# Teensy_Fan_Controller.net
KiCad netlist of a schematic drawn in EAGLE
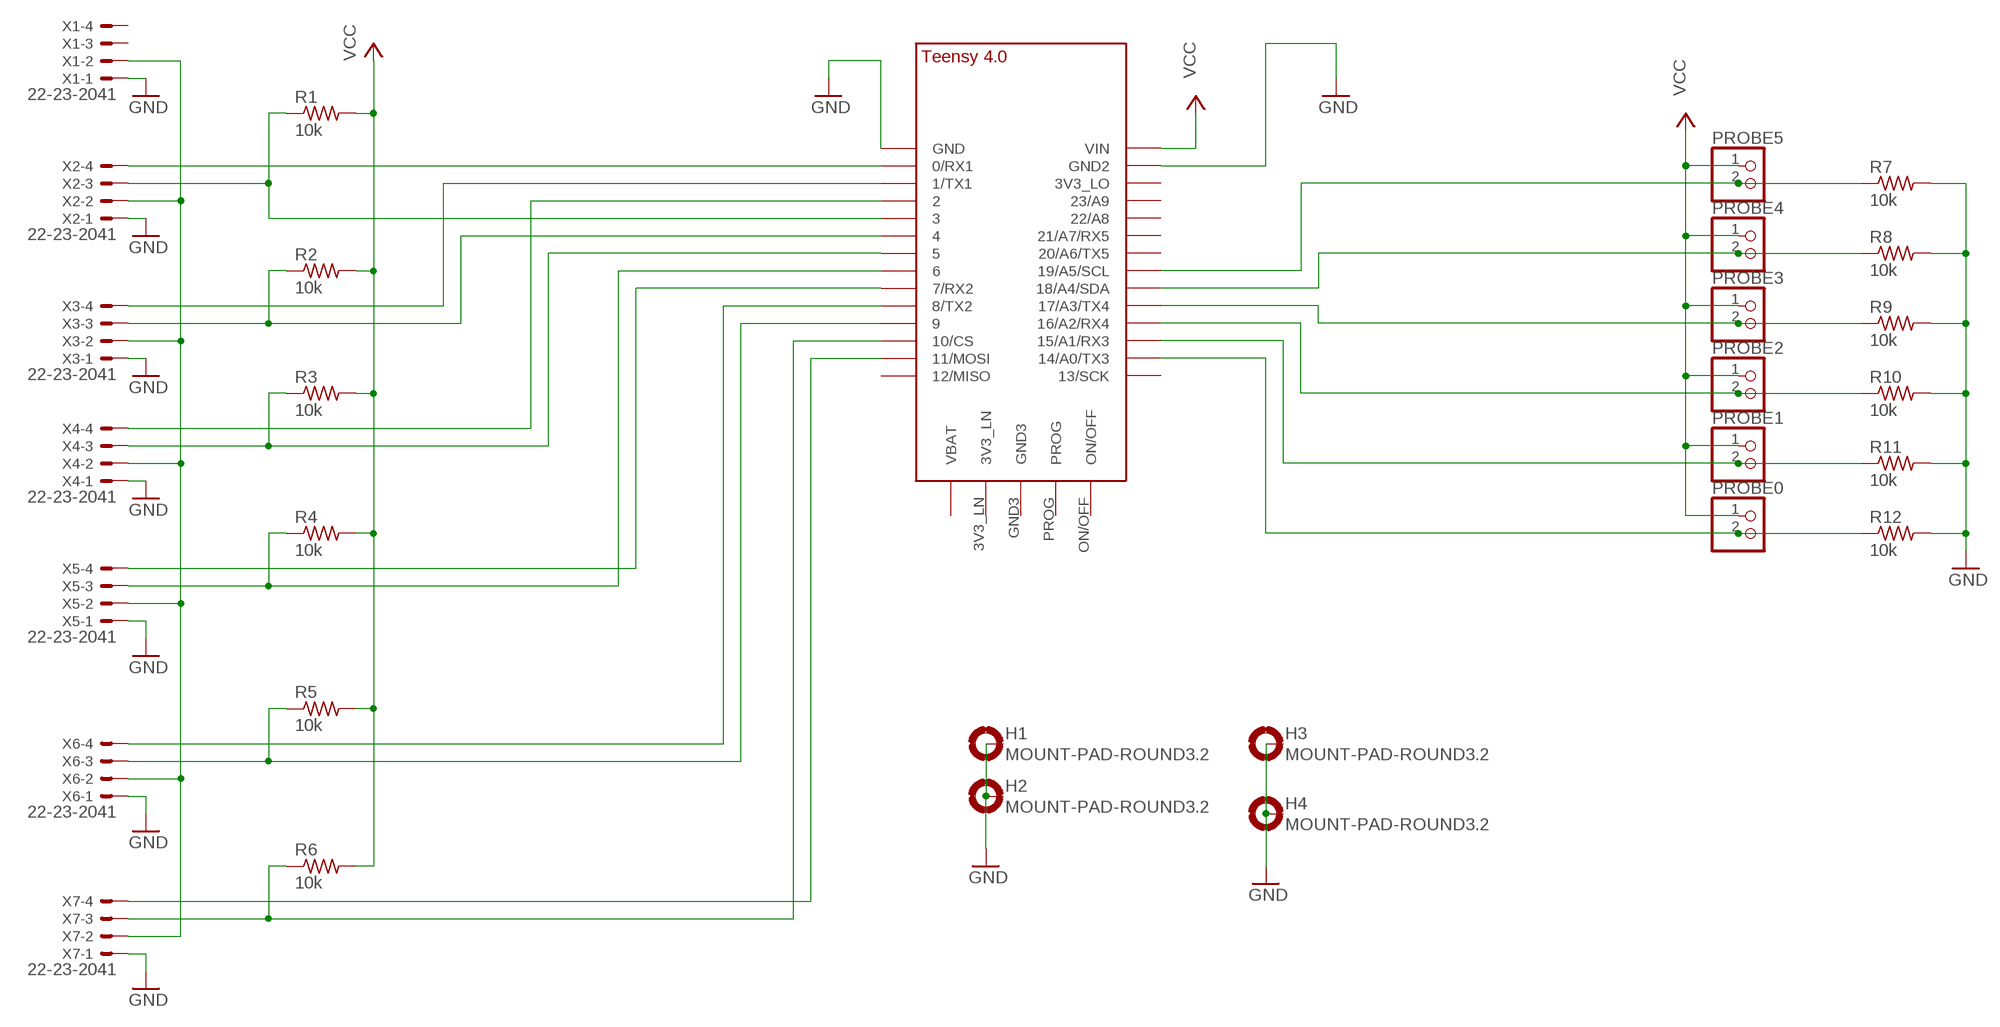
[diagram p0: schematic, sheet 1]

(export (version "E")
  (design (tool "Eeschema 10.0.6"))
  (components
    (comp (ref "H1")
      (value "MOUNT-PAD-ROUND3.2")
      (footprint "eagle-import:3,2-PAD")
      (libsource (lib "eagle-import") (part "MOUNT-PAD-ROUND3.2"))
    )
    (comp (ref "H2")
      (value "MOUNT-PAD-ROUND3.2")
      (footprint "eagle-import:3,2-PAD")
      (libsource (lib "eagle-import") (part "MOUNT-PAD-ROUND3.2"))
    )
    (comp (ref "H3")
      (value "MOUNT-PAD-ROUND3.2")
      (footprint "eagle-import:3,2-PAD")
      (libsource (lib "eagle-import") (part "MOUNT-PAD-ROUND3.2"))
    )
    (comp (ref "H4")
      (value "MOUNT-PAD-ROUND3.2")
      (footprint "eagle-import:3,2-PAD")
      (libsource (lib "eagle-import") (part "MOUNT-PAD-ROUND3.2"))
    )
    (comp (ref "PROBE0")
      (value "PINHD-1X2")
      (footprint "eagle-import:1X02")
      (libsource (lib "eagle-import") (part "PINHD-1X2"))
    )
    (comp (ref "PROBE1")
      (value "PINHD-1X2")
      (footprint "eagle-import:1X02")
      (libsource (lib "eagle-import") (part "PINHD-1X2"))
    )
    (comp (ref "PROBE2")
      (value "PINHD-1X2")
      (footprint "eagle-import:1X02")
      (libsource (lib "eagle-import") (part "PINHD-1X2"))
    )
    (comp (ref "PROBE3")
      (value "PINHD-1X2")
      (footprint "eagle-import:1X02")
      (libsource (lib "eagle-import") (part "PINHD-1X2"))
    )
    (comp (ref "PROBE4")
      (value "PINHD-1X2")
      (footprint "eagle-import:1X02")
      (libsource (lib "eagle-import") (part "PINHD-1X2"))
    )
    (comp (ref "PROBE5")
      (value "PINHD-1X2")
      (footprint "eagle-import:1X02")
      (libsource (lib "eagle-import") (part "PINHD-1X2"))
    )
    (comp (ref "R1")
      (value "10k")
      (footprint "eagle-import:0207_10")
      (libsource (lib "eagle-import") (part "R-US_0207/10"))
    )
    (comp (ref "R2")
      (value "10k")
      (footprint "eagle-import:0207_10")
      (libsource (lib "eagle-import") (part "R-US_0207/10"))
    )
    (comp (ref "R3")
      (value "10k")
      (footprint "eagle-import:0207_10")
      (libsource (lib "eagle-import") (part "R-US_0207/10"))
    )
    (comp (ref "R4")
      (value "10k")
      (footprint "eagle-import:0207_10")
      (libsource (lib "eagle-import") (part "R-US_0207/10"))
    )
    (comp (ref "R5")
      (value "10k")
      (footprint "eagle-import:0207_10")
      (libsource (lib "eagle-import") (part "R-US_0207/10"))
    )
    (comp (ref "R6")
      (value "10k")
      (footprint "eagle-import:0207_10")
      (libsource (lib "eagle-import") (part "R-US_0207/10"))
    )
    (comp (ref "R7")
      (value "10k")
      (footprint "eagle-import:0207_10")
      (libsource (lib "eagle-import") (part "R-US_0207/10"))
    )
    (comp (ref "R8")
      (value "10k")
      (footprint "eagle-import:0207_10")
      (libsource (lib "eagle-import") (part "R-US_0207/10"))
    )
    (comp (ref "R9")
      (value "10k")
      (footprint "eagle-import:0207_10")
      (libsource (lib "eagle-import") (part "R-US_0207/10"))
    )
    (comp (ref "R10")
      (value "10k")
      (footprint "eagle-import:0207_10")
      (libsource (lib "eagle-import") (part "R-US_0207/10"))
    )
    (comp (ref "R11")
      (value "10k")
      (footprint "eagle-import:0207_10")
      (libsource (lib "eagle-import") (part "R-US_0207/10"))
    )
    (comp (ref "R12")
      (value "10k")
      (footprint "eagle-import:0207_10")
      (libsource (lib "eagle-import") (part "R-US_0207/10"))
    )
    (comp (ref "U$2")
      (value "TEENSY_4.0")
      (footprint "eagle-import:TEENSY_4.0")
      (libsource (lib "eagle-import") (part "TEENSY_4.0"))
    )
    (comp (ref "X1")
      (value "22-23-2041")
      (footprint "eagle-import:22-23-2041")
      (fields (field (name "MF") "MOLEX"))
      (libsource (lib "eagle-import") (part "22-23-2041"))
    )
    (comp (ref "X2")
      (value "22-23-2041")
      (footprint "eagle-import:22-23-2041")
      (fields (field (name "MF") "MOLEX"))
      (libsource (lib "eagle-import") (part "22-23-2041"))
    )
    (comp (ref "X3")
      (value "22-23-2041")
      (footprint "eagle-import:22-23-2041")
      (fields (field (name "MF") "MOLEX"))
      (libsource (lib "eagle-import") (part "22-23-2041"))
    )
    (comp (ref "X4")
      (value "22-23-2041")
      (footprint "eagle-import:22-23-2041")
      (fields (field (name "MF") "MOLEX"))
      (libsource (lib "eagle-import") (part "22-23-2041"))
    )
    (comp (ref "X5")
      (value "22-23-2041")
      (footprint "eagle-import:22-23-2041")
      (fields (field (name "MF") "MOLEX"))
      (libsource (lib "eagle-import") (part "22-23-2041"))
    )
    (comp (ref "X6")
      (value "22-23-2041")
      (footprint "eagle-import:22-23-2041")
      (fields (field (name "MF") "MOLEX"))
      (libsource (lib "eagle-import") (part "22-23-2041"))
    )
    (comp (ref "X7")
      (value "22-23-2041")
      (footprint "eagle-import:22-23-2041")
      (fields (field (name "MF") "MOLEX"))
      (libsource (lib "eagle-import") (part "22-23-2041"))
    )
  )
  (nets
    (net (code "1") (name "GND") (class "Default")
      (node (ref "H1") (pin "B3,2") (pinfunction "MOUNT_B3,2") (pintype "passive"))
      (node (ref "H2") (pin "B3,2") (pinfunction "MOUNT_B3,2") (pintype "passive"))
      (node (ref "H3") (pin "B3,2") (pinfunction "MOUNT_B3,2") (pintype "passive"))
      (node (ref "H4") (pin "B3,2") (pinfunction "MOUNT_B3,2") (pintype "passive"))
      (node (ref "R10") (pin "2") (pinfunction "2_2") (pintype "passive"))
      (node (ref "R11") (pin "2") (pinfunction "2_2") (pintype "passive"))
      (node (ref "R12") (pin "2") (pinfunction "2_2") (pintype "passive"))
      (node (ref "R7") (pin "2") (pinfunction "2_2") (pintype "passive"))
      (node (ref "R8") (pin "2") (pinfunction "2_2") (pintype "passive"))
      (node (ref "R9") (pin "2") (pinfunction "2_2") (pintype "passive"))
      (node (ref "U$2") (pin "GND") (pinfunction "GND_GND") (pintype "bidirectional"))
      (node (ref "U$2") (pin "GND2") (pinfunction "GND2_GND2") (pintype "bidirectional"))
      (node (ref "X1") (pin "1") (pinfunction "S_1") (pintype "passive"))
      (node (ref "X2") (pin "1") (pinfunction "S_1") (pintype "passive"))
      (node (ref "X3") (pin "1") (pinfunction "S_1") (pintype "passive"))
      (node (ref "X4") (pin "1") (pinfunction "S_1") (pintype "passive"))
      (node (ref "X5") (pin "1") (pinfunction "S_1") (pintype "passive"))
      (node (ref "X6") (pin "1") (pinfunction "S_1") (pintype "passive"))
      (node (ref "X7") (pin "1") (pinfunction "S_1") (pintype "passive"))
    )
    (net (code "2") (name "Net-(PROBE4-Pad2)") (class "Default")
      (node (ref "PROBE4") (pin "2") (pinfunction "2_2") (pintype "passive"))
      (node (ref "R8") (pin "1") (pinfunction "1_1") (pintype "passive"))
      (node (ref "U$2") (pin "18/A4/SDA") (pinfunction "18/A4/SDA_18/A4/SDA") (pintype "bidirectional"))
    )
    (net (code "3") (name "Net-(PROBE5-Pad2)") (class "Default")
      (node (ref "PROBE5") (pin "2") (pinfunction "2_2") (pintype "passive"))
      (node (ref "R7") (pin "1") (pinfunction "1_1") (pintype "passive"))
      (node (ref "U$2") (pin "19/A5/SCL") (pinfunction "19/A5/SCL_19/A5/SCL") (pintype "bidirectional"))
    )
    (net (code "4") (name "Net-(U$2-0{slash}RX1)") (class "Default")
      (node (ref "U$2") (pin "0/RX") (pinfunction "0/RX1_0/RX") (pintype "bidirectional"))
      (node (ref "X2") (pin "4") (pinfunction "S_4") (pintype "passive"))
    )
    (net (code "5") (name "Net-(U$2-1{slash}TX1)") (class "Default")
      (node (ref "U$2") (pin "1/TX") (pinfunction "1/TX1_1/TX") (pintype "bidirectional"))
      (node (ref "X3") (pin "4") (pinfunction "S_4") (pintype "passive"))
    )
    (net (code "6") (name "Net-(U$2-3)") (class "Default")
      (node (ref "R1") (pin "1") (pinfunction "1_1") (pintype "passive"))
      (node (ref "U$2") (pin "3/CANTX") (pinfunction "3_3/CANTX") (pintype "bidirectional"))
      (node (ref "X2") (pin "3") (pinfunction "S_3") (pintype "passive"))
    )
    (net (code "7") (name "Net-(U$2-4)") (class "Default")
      (node (ref "R2") (pin "1") (pinfunction "1_1") (pintype "passive"))
      (node (ref "U$2") (pin "4/CANRX") (pinfunction "4_4/CANRX") (pintype "bidirectional"))
      (node (ref "X3") (pin "3") (pinfunction "S_3") (pintype "passive"))
    )
    (net (code "8") (name "Net-(U$2-7{slash}RX2)") (class "Default")
      (node (ref "U$2") (pin "7") (pinfunction "7/RX2_7") (pintype "bidirectional"))
      (node (ref "X5") (pin "4") (pinfunction "S_4") (pintype "passive"))
    )
    (net (code "9") (name "Net-(U$2-8{slash}TX2)") (class "Default")
      (node (ref "U$2") (pin "8") (pinfunction "8/TX2_8") (pintype "bidirectional"))
      (node (ref "X6") (pin "4") (pinfunction "S_4") (pintype "passive"))
    )
    (net (code "10") (name "Net-(U$2-9)") (class "Default")
      (node (ref "R5") (pin "1") (pinfunction "1_1") (pintype "passive"))
      (node (ref "U$2") (pin "9/CS") (pinfunction "9_9/CS") (pintype "bidirectional"))
      (node (ref "X6") (pin "3") (pinfunction "S_3") (pintype "passive"))
    )
    (net (code "11") (name "Net-(U$2-14{slash}A0{slash}TX3)") (class "Default")
      (node (ref "PROBE0") (pin "2") (pinfunction "2_2") (pintype "passive"))
      (node (ref "R12") (pin "1") (pinfunction "1_1") (pintype "passive"))
      (node (ref "U$2") (pin "14/A0") (pinfunction "14/A0/TX3_14/A0") (pintype "bidirectional"))
    )
    (net (code "12") (name "Net-(U$2-15{slash}A1{slash}RX3)") (class "Default")
      (node (ref "PROBE1") (pin "2") (pinfunction "2_2") (pintype "passive"))
      (node (ref "R11") (pin "1") (pinfunction "1_1") (pintype "passive"))
      (node (ref "U$2") (pin "15/A1") (pinfunction "15/A1/RX3_15/A1") (pintype "bidirectional"))
    )
    (net (code "13") (name "Net-(U$2-16{slash}A2{slash}RX4)") (class "Default")
      (node (ref "PROBE2") (pin "2") (pinfunction "2_2") (pintype "passive"))
      (node (ref "R10") (pin "1") (pinfunction "1_1") (pintype "passive"))
      (node (ref "U$2") (pin "16/A2") (pinfunction "16/A2/RX4_16/A2") (pintype "bidirectional"))
    )
    (net (code "14") (name "Net-(U$2-17{slash}A3{slash}TX4)") (class "Default")
      (node (ref "PROBE3") (pin "2") (pinfunction "2_2") (pintype "passive"))
      (node (ref "R9") (pin "1") (pinfunction "1_1") (pintype "passive"))
      (node (ref "U$2") (pin "17/A3") (pinfunction "17/A3/TX4_17/A3") (pintype "bidirectional"))
    )
    (net (code "15") (name "Net-(X1B-S)") (class "Default")
      (node (ref "X1") (pin "2") (pinfunction "S_2") (pintype "passive"))
      (node (ref "X2") (pin "2") (pinfunction "S_2") (pintype "passive"))
      (node (ref "X3") (pin "2") (pinfunction "S_2") (pintype "passive"))
      (node (ref "X4") (pin "2") (pinfunction "S_2") (pintype "passive"))
      (node (ref "X5") (pin "2") (pinfunction "S_2") (pintype "passive"))
      (node (ref "X6") (pin "2") (pinfunction "S_2") (pintype "passive"))
      (node (ref "X7") (pin "2") (pinfunction "S_2") (pintype "passive"))
    )
    (net (code "16") (name "Net-(X4C-S)") (class "Default")
      (node (ref "R3") (pin "1") (pinfunction "1_1") (pintype "passive"))
      (node (ref "U$2") (pin "5") (pinfunction "5_5") (pintype "bidirectional"))
      (node (ref "X4") (pin "3") (pinfunction "S_3") (pintype "passive"))
    )
    (net (code "17") (name "Net-(X4D-S)") (class "Default")
      (node (ref "U$2") (pin "2") (pinfunction "2_2") (pintype "bidirectional"))
      (node (ref "X4") (pin "4") (pinfunction "S_4") (pintype "passive"))
    )
    (net (code "18") (name "Net-(X5C-S)") (class "Default")
      (node (ref "R4") (pin "1") (pinfunction "1_1") (pintype "passive"))
      (node (ref "U$2") (pin "6") (pinfunction "6_6") (pintype "bidirectional"))
      (node (ref "X5") (pin "3") (pinfunction "S_3") (pintype "passive"))
    )
    (net (code "19") (name "Net-(X7C-S)") (class "Default")
      (node (ref "R6") (pin "1") (pinfunction "1_1") (pintype "passive"))
      (node (ref "U$2") (pin "10/CS") (pinfunction "10/CS_10/CS") (pintype "bidirectional"))
      (node (ref "X7") (pin "3") (pinfunction "S_3") (pintype "passive"))
    )
    (net (code "20") (name "Net-(X7D-S)") (class "Default")
      (node (ref "U$2") (pin "11/MOSI") (pinfunction "11/MOSI_11/MOSI") (pintype "bidirectional"))
      (node (ref "X7") (pin "4") (pinfunction "S_4") (pintype "passive"))
    )
    (net (code "21") (name "VCC") (class "Default")
      (node (ref "PROBE0") (pin "1") (pinfunction "1_1") (pintype "passive"))
      (node (ref "PROBE1") (pin "1") (pinfunction "1_1") (pintype "passive"))
      (node (ref "PROBE2") (pin "1") (pinfunction "1_1") (pintype "passive"))
      (node (ref "PROBE3") (pin "1") (pinfunction "1_1") (pintype "passive"))
      (node (ref "PROBE4") (pin "1") (pinfunction "1_1") (pintype "passive"))
      (node (ref "PROBE5") (pin "1") (pinfunction "1_1") (pintype "passive"))
      (node (ref "R1") (pin "2") (pinfunction "2_2") (pintype "passive"))
      (node (ref "R2") (pin "2") (pinfunction "2_2") (pintype "passive"))
      (node (ref "R3") (pin "2") (pinfunction "2_2") (pintype "passive"))
      (node (ref "R4") (pin "2") (pinfunction "2_2") (pintype "passive"))
      (node (ref "R5") (pin "2") (pinfunction "2_2") (pintype "passive"))
      (node (ref "R6") (pin "2") (pinfunction "2_2") (pintype "passive"))
      (node (ref "U$2") (pin "VIN") (pinfunction "VIN_VIN") (pintype "bidirectional"))
    )
    (net (code "22") (name "unconnected-(U$2-20{slash}A6{slash}TX5-Pad20{slash}A6)") (class "Default")
      (node (ref "U$2") (pin "20/A6") (pinfunction "20/A6/TX5_20/A6") (pintype "bidirectional"))
    )
    (net (code "23") (name "unconnected-(U$2-21{slash}A7{slash}RX5-Pad21{slash}A7)") (class "Default")
      (node (ref "U$2") (pin "21/A7") (pinfunction "21/A7/RX5_21/A7") (pintype "bidirectional"))
    )
    (net (code "24") (name "unconnected-(U$2-Pad3V3_LN)") (class "Default")
      (node (ref "U$2") (pin "3V3_LN") (pinfunction "3V3_LN_3V3_LN") (pintype "bidirectional"))
    )
    (net (code "25") (name "unconnected-(U$2-Pad3V3_LO)") (class "Default")
      (node (ref "U$2") (pin "3V3_LO") (pinfunction "3V3_LO_3V3_LO") (pintype "bidirectional"))
    )
    (net (code "26") (name "unconnected-(U$2-Pad12{slash}MISO)") (class "Default")
      (node (ref "U$2") (pin "12/MISO") (pinfunction "12/MISO_12/MISO") (pintype "bidirectional"))
    )
    (net (code "27") (name "unconnected-(U$2-Pad13{slash}SCK)") (class "Default")
      (node (ref "U$2") (pin "13/SCK") (pinfunction "13/SCK_13/SCK") (pintype "bidirectional"))
    )
    (net (code "28") (name "unconnected-(U$2-Pad22{slash}A8)") (class "Default")
      (node (ref "U$2") (pin "22/A8") (pinfunction "22/A8_22/A8") (pintype "bidirectional"))
    )
    (net (code "29") (name "unconnected-(U$2-Pad23{slash}A9)") (class "Default")
      (node (ref "U$2") (pin "23/A9") (pinfunction "23/A9_23/A9") (pintype "bidirectional"))
    )
    (net (code "30") (name "unconnected-(U$2-PadGND3)") (class "Default")
      (node (ref "U$2") (pin "GND3") (pinfunction "GND3_GND3") (pintype "bidirectional"))
    )
    (net (code "31") (name "unconnected-(U$2-PadON{slash}OFF)") (class "Default")
      (node (ref "U$2") (pin "ON/OFF") (pinfunction "ON/OFF_ON/OFF") (pintype "bidirectional"))
    )
    (net (code "32") (name "unconnected-(U$2-PadPROG)") (class "Default")
      (node (ref "U$2") (pin "PROG") (pinfunction "PROG_PROG") (pintype "bidirectional"))
    )
    (net (code "33") (name "unconnected-(U$2-VBAT-PadVBAT\\)") (class "Default")
      (node (ref "U$2") (pin "VBAT\\") (pinfunction "VBAT_VBAT\\") (pintype "bidirectional"))
    )
    (net (code "34") (name "unconnected-(X1C-S-Pad3)") (class "Default")
      (node (ref "X1") (pin "3") (pinfunction "S_3") (pintype "passive"))
    )
    (net (code "35") (name "unconnected-(X1D-S-Pad4)") (class "Default")
      (node (ref "X1") (pin "4") (pinfunction "S_4") (pintype "passive"))
    )
  )
)
